# FT232RL_REEL.net
KiCad netlist of a schematic drawn in EAGLE
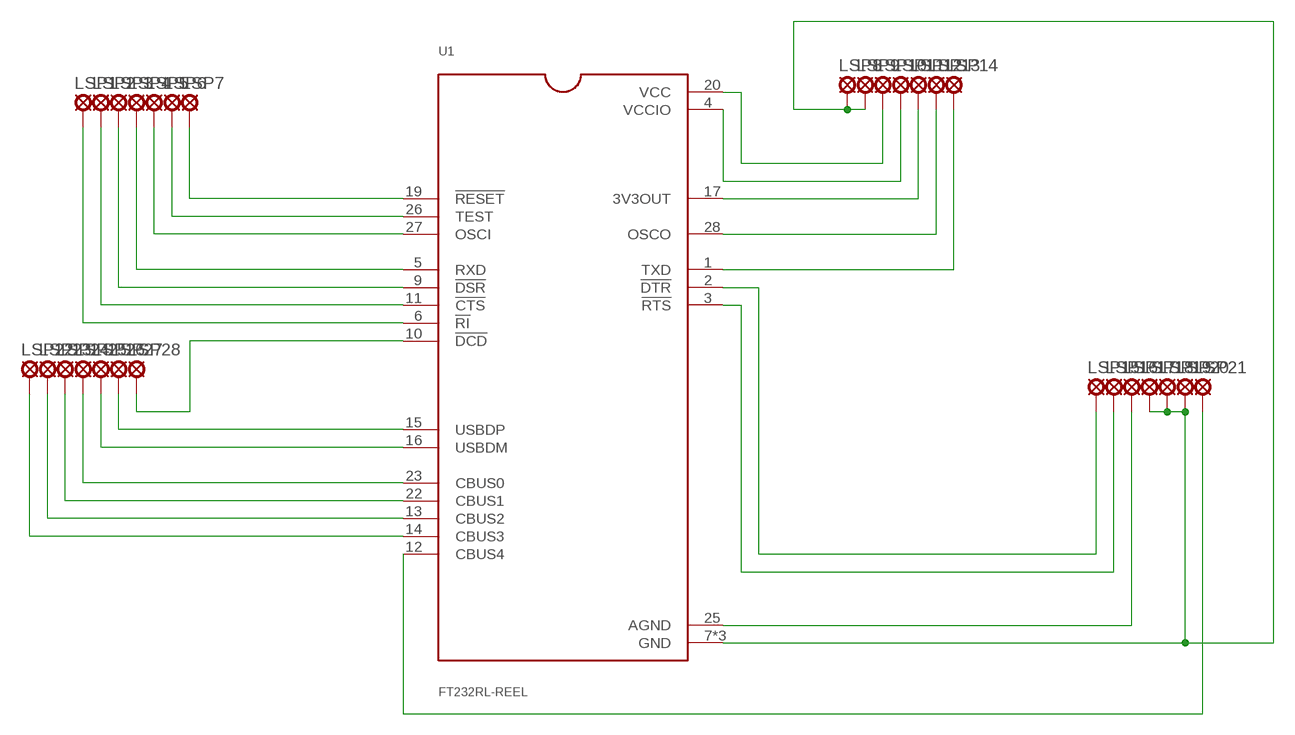
[diagram p0: schematic, sheet 1]

(export (version "E")
  (design (tool "Eeschema 10.0.6"))
  (components
    (comp (ref "LSP1")
      (value "LSP10_CLSP10_C")
      (footprint "eagle-import:LSP10_C")
      (libsource (lib "eagle-import") (part "LSP10_CLSP10_C"))
    )
    (comp (ref "LSP2")
      (value "LSP10_CLSP10_C")
      (footprint "eagle-import:LSP10_C")
      (libsource (lib "eagle-import") (part "LSP10_CLSP10_C"))
    )
    (comp (ref "LSP3")
      (value "LSP10_CLSP10_C")
      (footprint "eagle-import:LSP10_C")
      (libsource (lib "eagle-import") (part "LSP10_CLSP10_C"))
    )
    (comp (ref "LSP4")
      (value "LSP10_CLSP10_C")
      (footprint "eagle-import:LSP10_C")
      (libsource (lib "eagle-import") (part "LSP10_CLSP10_C"))
    )
    (comp (ref "LSP5")
      (value "LSP10_CLSP10_C")
      (footprint "eagle-import:LSP10_C")
      (libsource (lib "eagle-import") (part "LSP10_CLSP10_C"))
    )
    (comp (ref "LSP6")
      (value "LSP10_CLSP10_C")
      (footprint "eagle-import:LSP10_C")
      (libsource (lib "eagle-import") (part "LSP10_CLSP10_C"))
    )
    (comp (ref "LSP7")
      (value "LSP10_CLSP10_C")
      (footprint "eagle-import:LSP10_C")
      (libsource (lib "eagle-import") (part "LSP10_CLSP10_C"))
    )
    (comp (ref "LSP8")
      (value "LSP10_CLSP10_C")
      (footprint "eagle-import:LSP10_C")
      (libsource (lib "eagle-import") (part "LSP10_CLSP10_C"))
    )
    (comp (ref "LSP9")
      (value "LSP10_CLSP10_C")
      (footprint "eagle-import:LSP10_C")
      (libsource (lib "eagle-import") (part "LSP10_CLSP10_C"))
    )
    (comp (ref "LSP10")
      (value "LSP10_CLSP10_C")
      (footprint "eagle-import:LSP10_C")
      (libsource (lib "eagle-import") (part "LSP10_CLSP10_C"))
    )
    (comp (ref "LSP11")
      (value "LSP10_CLSP10_C")
      (footprint "eagle-import:LSP10_C")
      (libsource (lib "eagle-import") (part "LSP10_CLSP10_C"))
    )
    (comp (ref "LSP12")
      (value "LSP10_CLSP10_C")
      (footprint "eagle-import:LSP10_C")
      (libsource (lib "eagle-import") (part "LSP10_CLSP10_C"))
    )
    (comp (ref "LSP13")
      (value "LSP10_CLSP10_C")
      (footprint "eagle-import:LSP10_C")
      (libsource (lib "eagle-import") (part "LSP10_CLSP10_C"))
    )
    (comp (ref "LSP14")
      (value "LSP10_CLSP10_C")
      (footprint "eagle-import:LSP10_C")
      (libsource (lib "eagle-import") (part "LSP10_CLSP10_C"))
    )
    (comp (ref "LSP15")
      (value "LSP10_CLSP10_C")
      (footprint "eagle-import:LSP10_C")
      (libsource (lib "eagle-import") (part "LSP10_CLSP10_C"))
    )
    (comp (ref "LSP16")
      (value "LSP10_CLSP10_C")
      (footprint "eagle-import:LSP10_C")
      (libsource (lib "eagle-import") (part "LSP10_CLSP10_C"))
    )
    (comp (ref "LSP17")
      (value "LSP10_CLSP10_C")
      (footprint "eagle-import:LSP10_C")
      (libsource (lib "eagle-import") (part "LSP10_CLSP10_C"))
    )
    (comp (ref "LSP18")
      (value "LSP10_CLSP10_C")
      (footprint "eagle-import:LSP10_C")
      (libsource (lib "eagle-import") (part "LSP10_CLSP10_C"))
    )
    (comp (ref "LSP19")
      (value "LSP10_CLSP10_C")
      (footprint "eagle-import:LSP10_C")
      (libsource (lib "eagle-import") (part "LSP10_CLSP10_C"))
    )
    (comp (ref "LSP20")
      (value "LSP10_CLSP10_C")
      (footprint "eagle-import:LSP10_C")
      (libsource (lib "eagle-import") (part "LSP10_CLSP10_C"))
    )
    (comp (ref "LSP21")
      (value "LSP10_CLSP10_C")
      (footprint "eagle-import:LSP10_C")
      (libsource (lib "eagle-import") (part "LSP10_CLSP10_C"))
    )
    (comp (ref "LSP22")
      (value "LSP10_CLSP10_C")
      (footprint "eagle-import:LSP10_C")
      (libsource (lib "eagle-import") (part "LSP10_CLSP10_C"))
    )
    (comp (ref "LSP23")
      (value "LSP10_CLSP10_C")
      (footprint "eagle-import:LSP10_C")
      (libsource (lib "eagle-import") (part "LSP10_CLSP10_C"))
    )
    (comp (ref "LSP24")
      (value "LSP10_CLSP10_C")
      (footprint "eagle-import:LSP10_C")
      (libsource (lib "eagle-import") (part "LSP10_CLSP10_C"))
    )
    (comp (ref "LSP25")
      (value "LSP10_CLSP10_C")
      (footprint "eagle-import:LSP10_C")
      (libsource (lib "eagle-import") (part "LSP10_CLSP10_C"))
    )
    (comp (ref "LSP26")
      (value "LSP10_CLSP10_C")
      (footprint "eagle-import:LSP10_C")
      (libsource (lib "eagle-import") (part "LSP10_CLSP10_C"))
    )
    (comp (ref "LSP27")
      (value "LSP10_CLSP10_C")
      (footprint "eagle-import:LSP10_C")
      (libsource (lib "eagle-import") (part "LSP10_CLSP10_C"))
    )
    (comp (ref "LSP28")
      (value "LSP10_CLSP10_C")
      (footprint "eagle-import:LSP10_C")
      (libsource (lib "eagle-import") (part "LSP10_CLSP10_C"))
    )
    (comp (ref "U1")
      (value "FT232RL-REEL")
      (footprint "eagle-import:SOP65P780X200-28N")
      (fields (field (name "DIGI-KEY_PART_NUMBER") "768-1007-1-ND") (field (name "MF") "FTDI,"))
      (libsource (lib "eagle-import") (part "FT232RL-REEL"))
    )
  )
  (nets
    (net (code "1") (name "Net-(LSP1-MP)") (class "Default")
      (node (ref "LSP1") (pin "P$1") (pinfunction "MP_P$1") (pintype "passive"))
      (node (ref "U1") (pin "6") (pinfunction "~{RI}_6") (pintype "input"))
    )
    (net (code "2") (name "Net-(LSP2-MP)") (class "Default")
      (node (ref "LSP2") (pin "P$1") (pinfunction "MP_P$1") (pintype "passive"))
      (node (ref "U1") (pin "11") (pinfunction "~{CTS}_11") (pintype "input"))
    )
    (net (code "3") (name "Net-(LSP3-MP)") (class "Default")
      (node (ref "LSP3") (pin "P$1") (pinfunction "MP_P$1") (pintype "passive"))
      (node (ref "U1") (pin "9") (pinfunction "~{DSR}_9") (pintype "input"))
    )
    (net (code "4") (name "Net-(LSP4-MP)") (class "Default")
      (node (ref "LSP4") (pin "P$1") (pinfunction "MP_P$1") (pintype "passive"))
      (node (ref "U1") (pin "5") (pinfunction "RXD_5") (pintype "input"))
    )
    (net (code "5") (name "Net-(LSP5-MP)") (class "Default")
      (node (ref "LSP5") (pin "P$1") (pinfunction "MP_P$1") (pintype "passive"))
      (node (ref "U1") (pin "27") (pinfunction "OSCI_27") (pintype "input"))
    )
    (net (code "6") (name "Net-(LSP6-MP)") (class "Default")
      (node (ref "LSP6") (pin "P$1") (pinfunction "MP_P$1") (pintype "passive"))
      (node (ref "U1") (pin "26") (pinfunction "TEST_26") (pintype "input"))
    )
    (net (code "7") (name "Net-(LSP7-MP)") (class "Default")
      (node (ref "LSP7") (pin "P$1") (pinfunction "MP_P$1") (pintype "passive"))
      (node (ref "U1") (pin "19") (pinfunction "~{RESET}_19") (pintype "input"))
    )
    (net (code "8") (name "Net-(LSP10-MP)") (class "Default")
      (node (ref "LSP10") (pin "P$1") (pinfunction "MP_P$1") (pintype "passive"))
      (node (ref "U1") (pin "20") (pinfunction "VCC_20") (pintype "power_in"))
    )
    (net (code "9") (name "Net-(LSP11-MP)") (class "Default")
      (node (ref "LSP11") (pin "P$1") (pinfunction "MP_P$1") (pintype "passive"))
      (node (ref "U1") (pin "4") (pinfunction "VCCIO_4") (pintype "power_in"))
    )
    (net (code "10") (name "Net-(LSP12-MP)") (class "Default")
      (node (ref "LSP12") (pin "P$1") (pinfunction "MP_P$1") (pintype "passive"))
      (node (ref "U1") (pin "17") (pinfunction "3V3OUT_17") (pintype "output"))
    )
    (net (code "11") (name "Net-(LSP13-MP)") (class "Default")
      (node (ref "LSP13") (pin "P$1") (pinfunction "MP_P$1") (pintype "passive"))
      (node (ref "U1") (pin "28") (pinfunction "OSCO_28") (pintype "output"))
    )
    (net (code "12") (name "Net-(LSP14-MP)") (class "Default")
      (node (ref "LSP14") (pin "P$1") (pinfunction "MP_P$1") (pintype "passive"))
      (node (ref "U1") (pin "1") (pinfunction "TXD_1") (pintype "output"))
    )
    (net (code "13") (name "Net-(LSP15-MP)") (class "Default")
      (node (ref "LSP15") (pin "P$1") (pinfunction "MP_P$1") (pintype "passive"))
      (node (ref "U1") (pin "2") (pinfunction "~{DTR}_2") (pintype "output"))
    )
    (net (code "14") (name "Net-(LSP16-MP)") (class "Default")
      (node (ref "LSP16") (pin "P$1") (pinfunction "MP_P$1") (pintype "passive"))
      (node (ref "U1") (pin "3") (pinfunction "~{RTS}_3") (pintype "output"))
    )
    (net (code "15") (name "Net-(LSP17-MP)") (class "Default")
      (node (ref "LSP17") (pin "P$1") (pinfunction "MP_P$1") (pintype "passive"))
      (node (ref "U1") (pin "25") (pinfunction "AGND_25") (pintype "passive"))
    )
    (net (code "16") (name "Net-(LSP18-MP)") (class "Default")
      (node (ref "LSP18") (pin "P$1") (pinfunction "MP_P$1") (pintype "passive"))
      (node (ref "LSP19") (pin "P$1") (pinfunction "MP_P$1") (pintype "passive"))
      (node (ref "LSP20") (pin "P$1") (pinfunction "MP_P$1") (pintype "passive"))
      (node (ref "LSP8") (pin "P$1") (pinfunction "MP_P$1") (pintype "passive"))
      (node (ref "LSP9") (pin "P$1") (pinfunction "MP_P$1") (pintype "passive"))
      (node (ref "U1") (pin "18") (pinfunction "GND_18") (pintype "passive"))
      (node (ref "U1") (pin "21") (pinfunction "GND_21") (pintype "passive"))
      (node (ref "U1") (pin "7") (pinfunction "GND_7") (pintype "passive"))
    )
    (net (code "17") (name "Net-(LSP21-MP)") (class "Default")
      (node (ref "LSP21") (pin "P$1") (pinfunction "MP_P$1") (pintype "passive"))
      (node (ref "U1") (pin "12") (pinfunction "CBUS4_12") (pintype "bidirectional"))
    )
    (net (code "18") (name "Net-(LSP22-MP)") (class "Default")
      (node (ref "LSP22") (pin "P$1") (pinfunction "MP_P$1") (pintype "passive"))
      (node (ref "U1") (pin "14") (pinfunction "CBUS3_14") (pintype "bidirectional"))
    )
    (net (code "19") (name "Net-(LSP23-MP)") (class "Default")
      (node (ref "LSP23") (pin "P$1") (pinfunction "MP_P$1") (pintype "passive"))
      (node (ref "U1") (pin "13") (pinfunction "CBUS2_13") (pintype "bidirectional"))
    )
    (net (code "20") (name "Net-(LSP24-MP)") (class "Default")
      (node (ref "LSP24") (pin "P$1") (pinfunction "MP_P$1") (pintype "passive"))
      (node (ref "U1") (pin "22") (pinfunction "CBUS1_22") (pintype "bidirectional"))
    )
    (net (code "21") (name "Net-(LSP25-MP)") (class "Default")
      (node (ref "LSP25") (pin "P$1") (pinfunction "MP_P$1") (pintype "passive"))
      (node (ref "U1") (pin "23") (pinfunction "CBUS0_23") (pintype "bidirectional"))
    )
    (net (code "22") (name "Net-(LSP26-MP)") (class "Default")
      (node (ref "LSP26") (pin "P$1") (pinfunction "MP_P$1") (pintype "passive"))
      (node (ref "U1") (pin "16") (pinfunction "USBDM_16") (pintype "bidirectional"))
    )
    (net (code "23") (name "Net-(LSP27-MP)") (class "Default")
      (node (ref "LSP27") (pin "P$1") (pinfunction "MP_P$1") (pintype "passive"))
      (node (ref "U1") (pin "15") (pinfunction "USBDP_15") (pintype "bidirectional"))
    )
    (net (code "24") (name "Net-(LSP28-MP)") (class "Default")
      (node (ref "LSP28") (pin "P$1") (pinfunction "MP_P$1") (pintype "passive"))
      (node (ref "U1") (pin "10") (pinfunction "~{DCD}_10") (pintype "input"))
    )
  )
)
